# wykonawczy.net
KiCad netlist of a schematic drawn in EAGLE
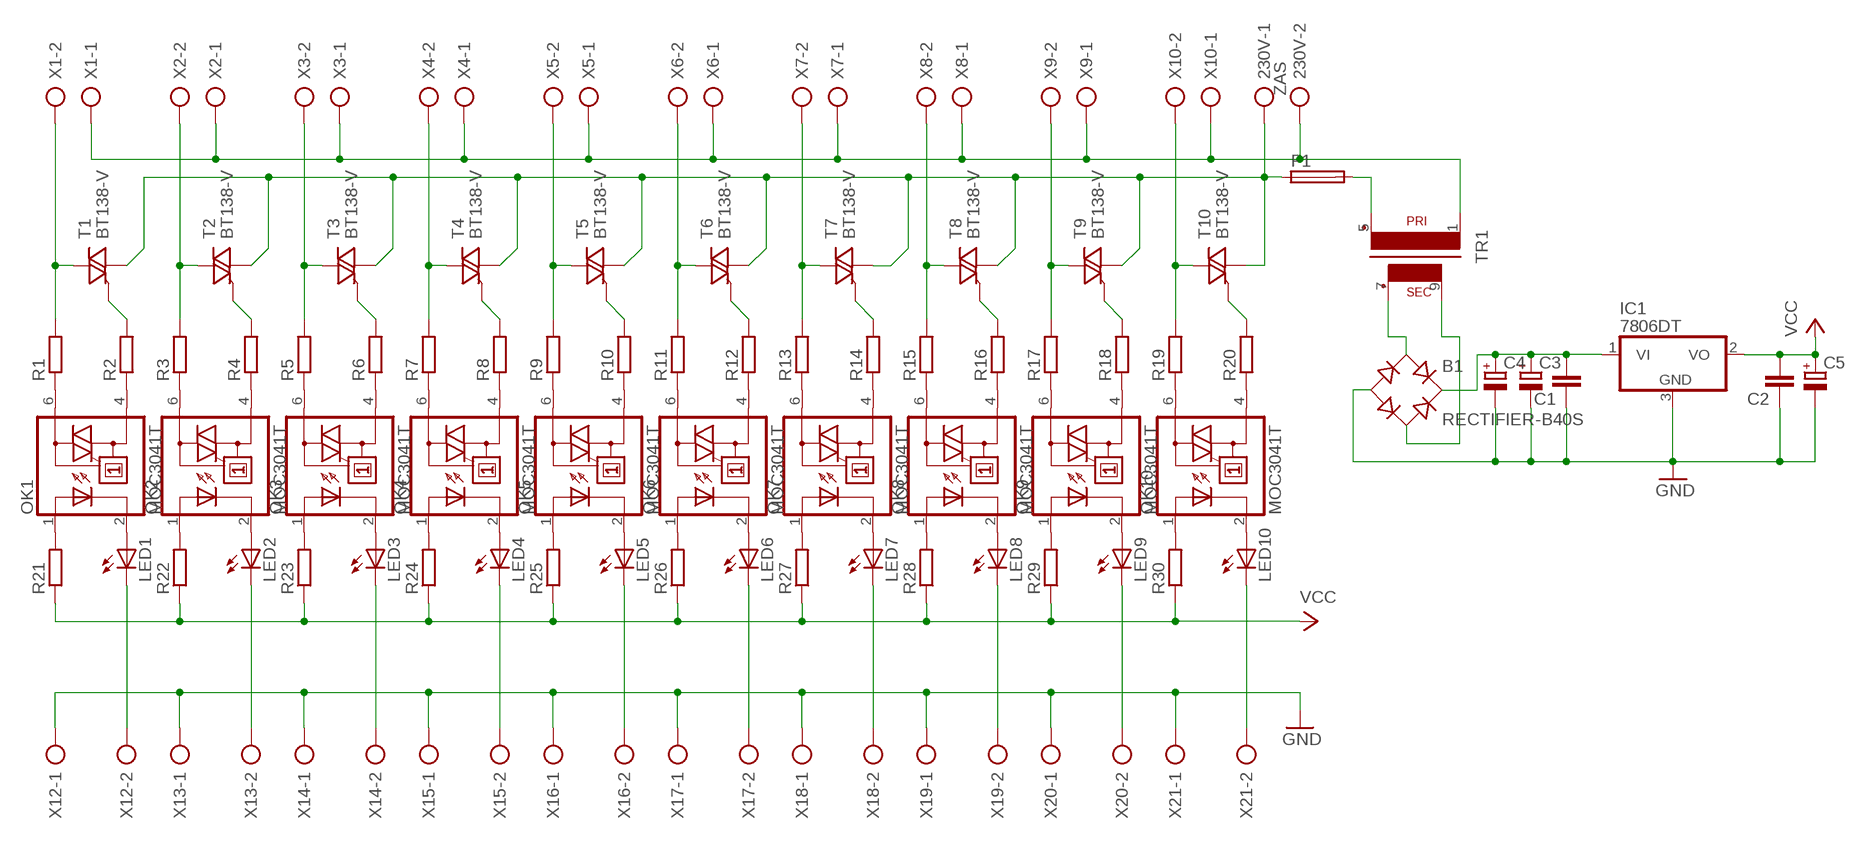
[diagram p0: schematic, sheet 1]

(export (version "E")
  (design (tool "Eeschema 10.0.6"))
  (components
    (comp (ref "230V")
      (value "ZAS")
      (footprint "eagle-import:AK500_2")
      (libsource (lib "eagle-import") (part "AK500/2"))
    )
    (comp (ref "B1")
      (value "RECTIFIER-B40S")
      (footprint "eagle-import:B40S")
      (libsource (lib "eagle-import") (part "RECTIFIER-B40S"))
    )
    (comp (ref "C1")
      (value "C-EU025-025X050")
      (footprint "eagle-import:C025-025X050")
      (libsource (lib "eagle-import") (part "C-EU025-025X050"))
    )
    (comp (ref "C2")
      (value "C-EU025-025X050")
      (footprint "eagle-import:C025-025X050")
      (libsource (lib "eagle-import") (part "C-EU025-025X050"))
    )
    (comp (ref "C3")
      (value "CPOL-EUE2.5-6")
      (footprint "eagle-import:E2,5-6")
      (libsource (lib "eagle-import") (part "CPOL-EUE2.5-6"))
    )
    (comp (ref "C4")
      (value "CPOL-EUE2.5-6")
      (footprint "eagle-import:E2,5-6")
      (libsource (lib "eagle-import") (part "CPOL-EUE2.5-6"))
    )
    (comp (ref "C5")
      (value "CPOL-EUE2.5-6")
      (footprint "eagle-import:E2,5-6")
      (libsource (lib "eagle-import") (part "CPOL-EUE2.5-6"))
    )
    (comp (ref "F1")
      (value "19560")
      (footprint "eagle-import:19560")
      (fields (field (name "MPN") "56000001009"))
      (libsource (lib "eagle-import") (part "19560"))
    )
    (comp (ref "IC1")
      (value "7806DT")
      (footprint "eagle-import:TO252")
      (libsource (lib "eagle-import") (part "78DT06"))
    )
    (comp (ref "LED1")
      (value "LED5MM")
      (footprint "eagle-import:LED5MM")
      (libsource (lib "eagle-import") (part "LED5MM"))
    )
    (comp (ref "LED2")
      (value "LED5MM")
      (footprint "eagle-import:LED5MM")
      (libsource (lib "eagle-import") (part "LED5MM"))
    )
    (comp (ref "LED3")
      (value "LED5MM")
      (footprint "eagle-import:LED5MM")
      (libsource (lib "eagle-import") (part "LED5MM"))
    )
    (comp (ref "LED4")
      (value "LED5MM")
      (footprint "eagle-import:LED5MM")
      (libsource (lib "eagle-import") (part "LED5MM"))
    )
    (comp (ref "LED5")
      (value "LED5MM")
      (footprint "eagle-import:LED5MM")
      (libsource (lib "eagle-import") (part "LED5MM"))
    )
    (comp (ref "LED6")
      (value "LED5MM")
      (footprint "eagle-import:LED5MM")
      (libsource (lib "eagle-import") (part "LED5MM"))
    )
    (comp (ref "LED7")
      (value "LED5MM")
      (footprint "eagle-import:LED5MM")
      (libsource (lib "eagle-import") (part "LED5MM"))
    )
    (comp (ref "LED8")
      (value "LED5MM")
      (footprint "eagle-import:LED5MM")
      (libsource (lib "eagle-import") (part "LED5MM"))
    )
    (comp (ref "LED9")
      (value "LED5MM")
      (footprint "eagle-import:LED5MM")
      (libsource (lib "eagle-import") (part "LED5MM"))
    )
    (comp (ref "LED10")
      (value "LED5MM")
      (footprint "eagle-import:LED5MM")
      (libsource (lib "eagle-import") (part "LED5MM"))
    )
    (comp (ref "OK1")
      (value "MOC3041T")
      (footprint "eagle-import:DIL06B")
      (libsource (lib "eagle-import") (part "MOC30T41"))
    )
    (comp (ref "OK2")
      (value "MOC3041T")
      (footprint "eagle-import:DIL06B")
      (libsource (lib "eagle-import") (part "MOC30T41"))
    )
    (comp (ref "OK3")
      (value "MOC3041T")
      (footprint "eagle-import:DIL06B")
      (libsource (lib "eagle-import") (part "MOC30T41"))
    )
    (comp (ref "OK4")
      (value "MOC3041T")
      (footprint "eagle-import:DIL06B")
      (libsource (lib "eagle-import") (part "MOC30T41"))
    )
    (comp (ref "OK5")
      (value "MOC3041T")
      (footprint "eagle-import:DIL06B")
      (libsource (lib "eagle-import") (part "MOC30T41"))
    )
    (comp (ref "OK6")
      (value "MOC3041T")
      (footprint "eagle-import:DIL06B")
      (libsource (lib "eagle-import") (part "MOC30T41"))
    )
    (comp (ref "OK7")
      (value "MOC3041T")
      (footprint "eagle-import:DIL06B")
      (libsource (lib "eagle-import") (part "MOC30T41"))
    )
    (comp (ref "OK8")
      (value "MOC3041T")
      (footprint "eagle-import:DIL06B")
      (libsource (lib "eagle-import") (part "MOC30T41"))
    )
    (comp (ref "OK9")
      (value "MOC3041T")
      (footprint "eagle-import:DIL06B")
      (libsource (lib "eagle-import") (part "MOC30T41"))
    )
    (comp (ref "OK10")
      (value "MOC3041T")
      (footprint "eagle-import:DIL06B")
      (libsource (lib "eagle-import") (part "MOC30T41"))
    )
    (comp (ref "R1")
      (value "R-EU_0204/7")
      (footprint "eagle-import:0204_7")
      (libsource (lib "eagle-import") (part "R-EU_0204/7"))
    )
    (comp (ref "R2")
      (value "R-EU_0204/7")
      (footprint "eagle-import:0204_7")
      (libsource (lib "eagle-import") (part "R-EU_0204/7"))
    )
    (comp (ref "R3")
      (value "R-EU_0204/7")
      (footprint "eagle-import:0204_7")
      (libsource (lib "eagle-import") (part "R-EU_0204/7"))
    )
    (comp (ref "R4")
      (value "R-EU_0204/7")
      (footprint "eagle-import:0204_7")
      (libsource (lib "eagle-import") (part "R-EU_0204/7"))
    )
    (comp (ref "R5")
      (value "R-EU_0204/7")
      (footprint "eagle-import:0204_7")
      (libsource (lib "eagle-import") (part "R-EU_0204/7"))
    )
    (comp (ref "R6")
      (value "R-EU_0204/7")
      (footprint "eagle-import:0204_7")
      (libsource (lib "eagle-import") (part "R-EU_0204/7"))
    )
    (comp (ref "R7")
      (value "R-EU_0204/7")
      (footprint "eagle-import:0204_7")
      (libsource (lib "eagle-import") (part "R-EU_0204/7"))
    )
    (comp (ref "R8")
      (value "R-EU_0204/7")
      (footprint "eagle-import:0204_7")
      (libsource (lib "eagle-import") (part "R-EU_0204/7"))
    )
    (comp (ref "R9")
      (value "R-EU_0204/7")
      (footprint "eagle-import:0204_7")
      (libsource (lib "eagle-import") (part "R-EU_0204/7"))
    )
    (comp (ref "R10")
      (value "R-EU_0204/7")
      (footprint "eagle-import:0204_7")
      (libsource (lib "eagle-import") (part "R-EU_0204/7"))
    )
    (comp (ref "R11")
      (value "R-EU_0204/7")
      (footprint "eagle-import:0204_7")
      (libsource (lib "eagle-import") (part "R-EU_0204/7"))
    )
    (comp (ref "R12")
      (value "R-EU_0204/7")
      (footprint "eagle-import:0204_7")
      (libsource (lib "eagle-import") (part "R-EU_0204/7"))
    )
    (comp (ref "R13")
      (value "R-EU_0204/7")
      (footprint "eagle-import:0204_7")
      (libsource (lib "eagle-import") (part "R-EU_0204/7"))
    )
    (comp (ref "R14")
      (value "R-EU_0204/7")
      (footprint "eagle-import:0204_7")
      (libsource (lib "eagle-import") (part "R-EU_0204/7"))
    )
    (comp (ref "R15")
      (value "R-EU_0204/7")
      (footprint "eagle-import:0204_7")
      (libsource (lib "eagle-import") (part "R-EU_0204/7"))
    )
    (comp (ref "R16")
      (value "R-EU_0204/7")
      (footprint "eagle-import:0204_7")
      (libsource (lib "eagle-import") (part "R-EU_0204/7"))
    )
    (comp (ref "R17")
      (value "R-EU_0204/7")
      (footprint "eagle-import:0204_7")
      (libsource (lib "eagle-import") (part "R-EU_0204/7"))
    )
    (comp (ref "R18")
      (value "R-EU_0204/7")
      (footprint "eagle-import:0204_7")
      (libsource (lib "eagle-import") (part "R-EU_0204/7"))
    )
    (comp (ref "R19")
      (value "R-EU_0204/7")
      (footprint "eagle-import:0204_7")
      (libsource (lib "eagle-import") (part "R-EU_0204/7"))
    )
    (comp (ref "R20")
      (value "R-EU_0204/7")
      (footprint "eagle-import:0204_7")
      (libsource (lib "eagle-import") (part "R-EU_0204/7"))
    )
    (comp (ref "R21")
      (value "R-EU_0204/7")
      (footprint "eagle-import:0204_7")
      (libsource (lib "eagle-import") (part "R-EU_0204/7"))
    )
    (comp (ref "R22")
      (value "R-EU_0204/7")
      (footprint "eagle-import:0204_7")
      (libsource (lib "eagle-import") (part "R-EU_0204/7"))
    )
    (comp (ref "R23")
      (value "R-EU_0204/7")
      (footprint "eagle-import:0204_7")
      (libsource (lib "eagle-import") (part "R-EU_0204/7"))
    )
    (comp (ref "R24")
      (value "R-EU_0204/7")
      (footprint "eagle-import:0204_7")
      (libsource (lib "eagle-import") (part "R-EU_0204/7"))
    )
    (comp (ref "R25")
      (value "R-EU_0204/7")
      (footprint "eagle-import:0204_7")
      (libsource (lib "eagle-import") (part "R-EU_0204/7"))
    )
    (comp (ref "R26")
      (value "R-EU_0204/7")
      (footprint "eagle-import:0204_7")
      (libsource (lib "eagle-import") (part "R-EU_0204/7"))
    )
    (comp (ref "R27")
      (value "R-EU_0204/7")
      (footprint "eagle-import:0204_7")
      (libsource (lib "eagle-import") (part "R-EU_0204/7"))
    )
    (comp (ref "R28")
      (value "R-EU_0204/7")
      (footprint "eagle-import:0204_7")
      (libsource (lib "eagle-import") (part "R-EU_0204/7"))
    )
    (comp (ref "R29")
      (value "R-EU_0204/7")
      (footprint "eagle-import:0204_7")
      (libsource (lib "eagle-import") (part "R-EU_0204/7"))
    )
    (comp (ref "R30")
      (value "R-EU_0204/7")
      (footprint "eagle-import:0204_7")
      (libsource (lib "eagle-import") (part "R-EU_0204/7"))
    )
    (comp (ref "T1")
      (value "BT138-V")
      (footprint "eagle-import:TO220BV")
      (libsource (lib "eagle-import") (part "BT138-V"))
    )
    (comp (ref "T2")
      (value "BT138-V")
      (footprint "eagle-import:TO220BV")
      (libsource (lib "eagle-import") (part "BT138-V"))
    )
    (comp (ref "T3")
      (value "BT138-V")
      (footprint "eagle-import:TO220BV")
      (libsource (lib "eagle-import") (part "BT138-V"))
    )
    (comp (ref "T4")
      (value "BT138-V")
      (footprint "eagle-import:TO220BV")
      (libsource (lib "eagle-import") (part "BT138-V"))
    )
    (comp (ref "T5")
      (value "BT138-V")
      (footprint "eagle-import:TO220BV")
      (libsource (lib "eagle-import") (part "BT138-V"))
    )
    (comp (ref "T6")
      (value "BT138-V")
      (footprint "eagle-import:TO220BV")
      (libsource (lib "eagle-import") (part "BT138-V"))
    )
    (comp (ref "T7")
      (value "BT138-V")
      (footprint "eagle-import:TO220BV")
      (libsource (lib "eagle-import") (part "BT138-V"))
    )
    (comp (ref "T8")
      (value "BT138-V")
      (footprint "eagle-import:TO220BV")
      (libsource (lib "eagle-import") (part "BT138-V"))
    )
    (comp (ref "T9")
      (value "BT138-V")
      (footprint "eagle-import:TO220BV")
      (libsource (lib "eagle-import") (part "BT138-V"))
    )
    (comp (ref "T10")
      (value "BT138-V")
      (footprint "eagle-import:TO220BV")
      (libsource (lib "eagle-import") (part "BT138-V"))
    )
    (comp (ref "TR1")
      (value "EI30-1")
      (footprint "eagle-import:EI30-1")
      (libsource (lib "eagle-import") (part "EI30-1"))
    )
    (comp (ref "X1")
      (value "AK500/2")
      (footprint "eagle-import:AK500_2")
      (libsource (lib "eagle-import") (part "AK500/2"))
    )
    (comp (ref "X2")
      (value "AK500/2")
      (footprint "eagle-import:AK500_2")
      (libsource (lib "eagle-import") (part "AK500/2"))
    )
    (comp (ref "X3")
      (value "AK500/2")
      (footprint "eagle-import:AK500_2")
      (libsource (lib "eagle-import") (part "AK500/2"))
    )
    (comp (ref "X4")
      (value "AK500/2")
      (footprint "eagle-import:AK500_2")
      (libsource (lib "eagle-import") (part "AK500/2"))
    )
    (comp (ref "X5")
      (value "AK500/2")
      (footprint "eagle-import:AK500_2")
      (libsource (lib "eagle-import") (part "AK500/2"))
    )
    (comp (ref "X6")
      (value "AK500/2")
      (footprint "eagle-import:AK500_2")
      (libsource (lib "eagle-import") (part "AK500/2"))
    )
    (comp (ref "X7")
      (value "AK500/2")
      (footprint "eagle-import:AK500_2")
      (libsource (lib "eagle-import") (part "AK500/2"))
    )
    (comp (ref "X8")
      (value "AK500/2")
      (footprint "eagle-import:AK500_2")
      (libsource (lib "eagle-import") (part "AK500/2"))
    )
    (comp (ref "X9")
      (value "AK500/2")
      (footprint "eagle-import:AK500_2")
      (libsource (lib "eagle-import") (part "AK500/2"))
    )
    (comp (ref "X10")
      (value "AK500/2")
      (footprint "eagle-import:AK500_2")
      (libsource (lib "eagle-import") (part "AK500/2"))
    )
    (comp (ref "X12")
      (value "AK500/2")
      (footprint "eagle-import:AK500_2")
      (libsource (lib "eagle-import") (part "AK500/2"))
    )
    (comp (ref "X13")
      (value "AK500/2")
      (footprint "eagle-import:AK500_2")
      (libsource (lib "eagle-import") (part "AK500/2"))
    )
    (comp (ref "X14")
      (value "AK500/2")
      (footprint "eagle-import:AK500_2")
      (libsource (lib "eagle-import") (part "AK500/2"))
    )
    (comp (ref "X15")
      (value "AK500/2")
      (footprint "eagle-import:AK500_2")
      (libsource (lib "eagle-import") (part "AK500/2"))
    )
    (comp (ref "X16")
      (value "AK500/2")
      (footprint "eagle-import:AK500_2")
      (libsource (lib "eagle-import") (part "AK500/2"))
    )
    (comp (ref "X17")
      (value "AK500/2")
      (footprint "eagle-import:AK500_2")
      (libsource (lib "eagle-import") (part "AK500/2"))
    )
    (comp (ref "X18")
      (value "AK500/2")
      (footprint "eagle-import:AK500_2")
      (libsource (lib "eagle-import") (part "AK500/2"))
    )
    (comp (ref "X19")
      (value "AK500/2")
      (footprint "eagle-import:AK500_2")
      (libsource (lib "eagle-import") (part "AK500/2"))
    )
    (comp (ref "X20")
      (value "AK500/2")
      (footprint "eagle-import:AK500_2")
      (libsource (lib "eagle-import") (part "AK500/2"))
    )
    (comp (ref "X21")
      (value "AK500/2")
      (footprint "eagle-import:AK500_2")
      (libsource (lib "eagle-import") (part "AK500/2"))
    )
  )
  (nets
    (net (code "1") (name "GND") (class "Default")
      (node (ref "B1") (pin "-") (pinfunction "-_-") (pintype "passive"))
      (node (ref "C1") (pin "1") (pinfunction "1_1") (pintype "passive"))
      (node (ref "C2") (pin "1") (pinfunction "1_1") (pintype "passive"))
      (node (ref "C3") (pin "-") (pinfunction "-_-") (pintype "passive"))
      (node (ref "C4") (pin "-") (pinfunction "-_-") (pintype "passive"))
      (node (ref "C5") (pin "-") (pinfunction "-_-") (pintype "passive"))
      (node (ref "IC1") (pin "3") (pinfunction "GND_3") (pintype "passive"))
      (node (ref "X12") (pin "1") (pinfunction "KL_1") (pintype "passive"))
      (node (ref "X13") (pin "1") (pinfunction "KL_1") (pintype "passive"))
      (node (ref "X14") (pin "1") (pinfunction "KL_1") (pintype "passive"))
      (node (ref "X15") (pin "1") (pinfunction "KL_1") (pintype "passive"))
      (node (ref "X16") (pin "1") (pinfunction "KL_1") (pintype "passive"))
      (node (ref "X17") (pin "1") (pinfunction "KL_1") (pintype "passive"))
      (node (ref "X18") (pin "1") (pinfunction "KL_1") (pintype "passive"))
      (node (ref "X19") (pin "1") (pinfunction "KL_1") (pintype "passive"))
      (node (ref "X20") (pin "1") (pinfunction "KL_1") (pintype "passive"))
      (node (ref "X21") (pin "1") (pinfunction "KL_1") (pintype "passive"))
    )
    (net (code "2") (name "Net-(230VA-KL)") (class "Default")
      (node (ref "230V") (pin "1") (pinfunction "KL_1") (pintype "passive"))
      (node (ref "F1") (pin "1") (pinfunction "1_1") (pintype "passive"))
      (node (ref "T1") (pin "T1") (pinfunction "A1_T1") (pintype "passive"))
      (node (ref "T10") (pin "T1") (pinfunction "A1_T1") (pintype "passive"))
      (node (ref "T2") (pin "T1") (pinfunction "A1_T1") (pintype "passive"))
      (node (ref "T3") (pin "T1") (pinfunction "A1_T1") (pintype "passive"))
      (node (ref "T4") (pin "T1") (pinfunction "A1_T1") (pintype "passive"))
      (node (ref "T5") (pin "T1") (pinfunction "A1_T1") (pintype "passive"))
      (node (ref "T6") (pin "T1") (pinfunction "A1_T1") (pintype "passive"))
      (node (ref "T7") (pin "T1") (pinfunction "A1_T1") (pintype "passive"))
      (node (ref "T8") (pin "T1") (pinfunction "A1_T1") (pintype "passive"))
      (node (ref "T9") (pin "T1") (pinfunction "A1_T1") (pintype "passive"))
    )
    (net (code "3") (name "Net-(230VB-KL)") (class "Default")
      (node (ref "230V") (pin "2") (pinfunction "KL_2") (pintype "passive"))
      (node (ref "TR1") (pin "1") (pinfunction "P1_1") (pintype "passive"))
      (node (ref "X1") (pin "1") (pinfunction "KL_1") (pintype "passive"))
      (node (ref "X10") (pin "1") (pinfunction "KL_1") (pintype "passive"))
      (node (ref "X2") (pin "1") (pinfunction "KL_1") (pintype "passive"))
      (node (ref "X3") (pin "1") (pinfunction "KL_1") (pintype "passive"))
      (node (ref "X4") (pin "1") (pinfunction "KL_1") (pintype "passive"))
      (node (ref "X5") (pin "1") (pinfunction "KL_1") (pintype "passive"))
      (node (ref "X6") (pin "1") (pinfunction "KL_1") (pintype "passive"))
      (node (ref "X7") (pin "1") (pinfunction "KL_1") (pintype "passive"))
      (node (ref "X8") (pin "1") (pinfunction "KL_1") (pintype "passive"))
      (node (ref "X9") (pin "1") (pinfunction "KL_1") (pintype "passive"))
    )
    (net (code "4") (name "Net-(IC1-VI)") (class "Default")
      (node (ref "B1") (pin "+") (pinfunction "+_+") (pintype "passive"))
      (node (ref "C1") (pin "2") (pinfunction "2_2") (pintype "passive"))
      (node (ref "C3") (pin "+") (pinfunction "+_+") (pintype "passive"))
      (node (ref "C4") (pin "+") (pinfunction "+_+") (pintype "passive"))
      (node (ref "IC1") (pin "1") (pinfunction "VI_1") (pintype "input"))
    )
    (net (code "5") (name "Net-(LED1-C)") (class "Default")
      (node (ref "LED1") (pin "K") (pinfunction "C_K") (pintype "passive"))
      (node (ref "X12") (pin "2") (pinfunction "KL_2") (pintype "passive"))
    )
    (net (code "6") (name "Net-(LED2-C)") (class "Default")
      (node (ref "LED2") (pin "K") (pinfunction "C_K") (pintype "passive"))
      (node (ref "X13") (pin "2") (pinfunction "KL_2") (pintype "passive"))
    )
    (net (code "7") (name "Net-(LED3-C)") (class "Default")
      (node (ref "LED3") (pin "K") (pinfunction "C_K") (pintype "passive"))
      (node (ref "X14") (pin "2") (pinfunction "KL_2") (pintype "passive"))
    )
    (net (code "8") (name "Net-(LED4-C)") (class "Default")
      (node (ref "LED4") (pin "K") (pinfunction "C_K") (pintype "passive"))
      (node (ref "X15") (pin "2") (pinfunction "KL_2") (pintype "passive"))
    )
    (net (code "9") (name "Net-(LED5-C)") (class "Default")
      (node (ref "LED5") (pin "K") (pinfunction "C_K") (pintype "passive"))
      (node (ref "X16") (pin "2") (pinfunction "KL_2") (pintype "passive"))
    )
    (net (code "10") (name "Net-(LED6-C)") (class "Default")
      (node (ref "LED6") (pin "K") (pinfunction "C_K") (pintype "passive"))
      (node (ref "X17") (pin "2") (pinfunction "KL_2") (pintype "passive"))
    )
    (net (code "11") (name "Net-(LED7-C)") (class "Default")
      (node (ref "LED7") (pin "K") (pinfunction "C_K") (pintype "passive"))
      (node (ref "X18") (pin "2") (pinfunction "KL_2") (pintype "passive"))
    )
    (net (code "12") (name "Net-(LED8-C)") (class "Default")
      (node (ref "LED8") (pin "K") (pinfunction "C_K") (pintype "passive"))
      (node (ref "X19") (pin "2") (pinfunction "KL_2") (pintype "passive"))
    )
    (net (code "13") (name "Net-(LED9-C)") (class "Default")
      (node (ref "LED9") (pin "K") (pinfunction "C_K") (pintype "passive"))
      (node (ref "X20") (pin "2") (pinfunction "KL_2") (pintype "passive"))
    )
    (net (code "14") (name "Net-(LED10-C)") (class "Default")
      (node (ref "LED10") (pin "K") (pinfunction "C_K") (pintype "passive"))
      (node (ref "X21") (pin "2") (pinfunction "KL_2") (pintype "passive"))
    )
    (net (code "15") (name "Net-(OK1-A)") (class "Default")
      (node (ref "OK1") (pin "1") (pinfunction "A_1") (pintype "passive"))
      (node (ref "R21") (pin "2") (pinfunction "2_2") (pintype "passive"))
    )
    (net (code "16") (name "Net-(OK1-A1)") (class "Default")
      (node (ref "OK1") (pin "4") (pinfunction "A1_4") (pintype "passive"))
      (node (ref "R2") (pin "1") (pinfunction "1_1") (pintype "passive"))
    )
    (net (code "17") (name "Net-(OK1-A2)") (class "Default")
      (node (ref "OK1") (pin "6") (pinfunction "A2_6") (pintype "passive"))
      (node (ref "R1") (pin "1") (pinfunction "1_1") (pintype "passive"))
    )
    (net (code "18") (name "Net-(OK1-C)") (class "Default")
      (node (ref "LED1") (pin "A") (pinfunction "A_A") (pintype "passive"))
      (node (ref "OK1") (pin "2") (pinfunction "C_2") (pintype "passive"))
    )
    (net (code "19") (name "Net-(OK2-A)") (class "Default")
      (node (ref "OK2") (pin "1") (pinfunction "A_1") (pintype "passive"))
      (node (ref "R22") (pin "2") (pinfunction "2_2") (pintype "passive"))
    )
    (net (code "20") (name "Net-(OK2-A1)") (class "Default")
      (node (ref "OK2") (pin "4") (pinfunction "A1_4") (pintype "passive"))
      (node (ref "R4") (pin "1") (pinfunction "1_1") (pintype "passive"))
    )
    (net (code "21") (name "Net-(OK2-A2)") (class "Default")
      (node (ref "OK2") (pin "6") (pinfunction "A2_6") (pintype "passive"))
      (node (ref "R3") (pin "1") (pinfunction "1_1") (pintype "passive"))
    )
    (net (code "22") (name "Net-(OK2-C)") (class "Default")
      (node (ref "LED2") (pin "A") (pinfunction "A_A") (pintype "passive"))
      (node (ref "OK2") (pin "2") (pinfunction "C_2") (pintype "passive"))
    )
    (net (code "23") (name "Net-(OK3-A)") (class "Default")
      (node (ref "OK3") (pin "1") (pinfunction "A_1") (pintype "passive"))
      (node (ref "R23") (pin "2") (pinfunction "2_2") (pintype "passive"))
    )
    (net (code "24") (name "Net-(OK3-A1)") (class "Default")
      (node (ref "OK3") (pin "4") (pinfunction "A1_4") (pintype "passive"))
      (node (ref "R6") (pin "1") (pinfunction "1_1") (pintype "passive"))
    )
    (net (code "25") (name "Net-(OK3-A2)") (class "Default")
      (node (ref "OK3") (pin "6") (pinfunction "A2_6") (pintype "passive"))
      (node (ref "R5") (pin "1") (pinfunction "1_1") (pintype "passive"))
    )
    (net (code "26") (name "Net-(OK3-C)") (class "Default")
      (node (ref "LED3") (pin "A") (pinfunction "A_A") (pintype "passive"))
      (node (ref "OK3") (pin "2") (pinfunction "C_2") (pintype "passive"))
    )
    (net (code "27") (name "Net-(OK4-A)") (class "Default")
      (node (ref "OK4") (pin "1") (pinfunction "A_1") (pintype "passive"))
      (node (ref "R24") (pin "2") (pinfunction "2_2") (pintype "passive"))
    )
    (net (code "28") (name "Net-(OK4-A1)") (class "Default")
      (node (ref "OK4") (pin "4") (pinfunction "A1_4") (pintype "passive"))
      (node (ref "R8") (pin "1") (pinfunction "1_1") (pintype "passive"))
    )
    (net (code "29") (name "Net-(OK4-A2)") (class "Default")
      (node (ref "OK4") (pin "6") (pinfunction "A2_6") (pintype "passive"))
      (node (ref "R7") (pin "1") (pinfunction "1_1") (pintype "passive"))
    )
    (net (code "30") (name "Net-(OK4-C)") (class "Default")
      (node (ref "LED4") (pin "A") (pinfunction "A_A") (pintype "passive"))
      (node (ref "OK4") (pin "2") (pinfunction "C_2") (pintype "passive"))
    )
    (net (code "31") (name "Net-(OK5-A)") (class "Default")
      (node (ref "OK5") (pin "1") (pinfunction "A_1") (pintype "passive"))
      (node (ref "R25") (pin "2") (pinfunction "2_2") (pintype "passive"))
    )
    (net (code "32") (name "Net-(OK5-A1)") (class "Default")
      (node (ref "OK5") (pin "4") (pinfunction "A1_4") (pintype "passive"))
      (node (ref "R10") (pin "1") (pinfunction "1_1") (pintype "passive"))
    )
    (net (code "33") (name "Net-(OK5-A2)") (class "Default")
      (node (ref "OK5") (pin "6") (pinfunction "A2_6") (pintype "passive"))
      (node (ref "R9") (pin "1") (pinfunction "1_1") (pintype "passive"))
    )
    (net (code "34") (name "Net-(OK5-C)") (class "Default")
      (node (ref "LED5") (pin "A") (pinfunction "A_A") (pintype "passive"))
      (node (ref "OK5") (pin "2") (pinfunction "C_2") (pintype "passive"))
    )
    (net (code "35") (name "Net-(OK6-A)") (class "Default")
      (node (ref "OK6") (pin "1") (pinfunction "A_1") (pintype "passive"))
      (node (ref "R26") (pin "2") (pinfunction "2_2") (pintype "passive"))
    )
    (net (code "36") (name "Net-(OK6-A1)") (class "Default")
      (node (ref "OK6") (pin "4") (pinfunction "A1_4") (pintype "passive"))
      (node (ref "R12") (pin "1") (pinfunction "1_1") (pintype "passive"))
    )
    (net (code "37") (name "Net-(OK6-A2)") (class "Default")
      (node (ref "OK6") (pin "6") (pinfunction "A2_6") (pintype "passive"))
      (node (ref "R11") (pin "1") (pinfunction "1_1") (pintype "passive"))
    )
    (net (code "38") (name "Net-(OK6-C)") (class "Default")
      (node (ref "LED6") (pin "A") (pinfunction "A_A") (pintype "passive"))
      (node (ref "OK6") (pin "2") (pinfunction "C_2") (pintype "passive"))
    )
    (net (code "39") (name "Net-(OK7-A)") (class "Default")
      (node (ref "OK7") (pin "1") (pinfunction "A_1") (pintype "passive"))
      (node (ref "R27") (pin "2") (pinfunction "2_2") (pintype "passive"))
    )
    (net (code "40") (name "Net-(OK7-A1)") (class "Default")
      (node (ref "OK7") (pin "4") (pinfunction "A1_4") (pintype "passive"))
      (node (ref "R14") (pin "1") (pinfunction "1_1") (pintype "passive"))
    )
    (net (code "41") (name "Net-(OK7-A2)") (class "Default")
      (node (ref "OK7") (pin "6") (pinfunction "A2_6") (pintype "passive"))
      (node (ref "R13") (pin "1") (pinfunction "1_1") (pintype "passive"))
    )
    (net (code "42") (name "Net-(OK7-C)") (class "Default")
      (node (ref "LED7") (pin "A") (pinfunction "A_A") (pintype "passive"))
      (node (ref "OK7") (pin "2") (pinfunction "C_2") (pintype "passive"))
    )
    (net (code "43") (name "Net-(OK8-A)") (class "Default")
      (node (ref "OK8") (pin "1") (pinfunction "A_1") (pintype "passive"))
      (node (ref "R28") (pin "2") (pinfunction "2_2") (pintype "passive"))
    )
    (net (code "44") (name "Net-(OK8-A1)") (class "Default")
      (node (ref "OK8") (pin "4") (pinfunction "A1_4") (pintype "passive"))
      (node (ref "R16") (pin "1") (pinfunction "1_1") (pintype "passive"))
    )
    (net (code "45") (name "Net-(OK8-A2)") (class "Default")
      (node (ref "OK8") (pin "6") (pinfunction "A2_6") (pintype "passive"))
      (node (ref "R15") (pin "1") (pinfunction "1_1") (pintype "passive"))
    )
    (net (code "46") (name "Net-(OK8-C)") (class "Default")
      (node (ref "LED8") (pin "A") (pinfunction "A_A") (pintype "passive"))
      (node (ref "OK8") (pin "2") (pinfunction "C_2") (pintype "passive"))
    )
    (net (code "47") (name "Net-(OK9-A)") (class "Default")
      (node (ref "OK9") (pin "1") (pinfunction "A_1") (pintype "passive"))
      (node (ref "R29") (pin "2") (pinfunction "2_2") (pintype "passive"))
    )
    (net (code "48") (name "Net-(OK9-A1)") (class "Default")
      (node (ref "OK9") (pin "4") (pinfunction "A1_4") (pintype "passive"))
      (node (ref "R18") (pin "1") (pinfunction "1_1") (pintype "passive"))
    )
    (net (code "49") (name "Net-(OK9-A2)") (class "Default")
      (node (ref "OK9") (pin "6") (pinfunction "A2_6") (pintype "passive"))
      (node (ref "R17") (pin "1") (pinfunction "1_1") (pintype "passive"))
    )
    (net (code "50") (name "Net-(OK9-C)") (class "Default")
      (node (ref "LED9") (pin "A") (pinfunction "A_A") (pintype "passive"))
      (node (ref "OK9") (pin "2") (pinfunction "C_2") (pintype "passive"))
    )
    (net (code "51") (name "Net-(OK10-A)") (class "Default")
      (node (ref "OK10") (pin "1") (pinfunction "A_1") (pintype "passive"))
      (node (ref "R30") (pin "2") (pinfunction "2_2") (pintype "passive"))
    )
    (net (code "52") (name "Net-(OK10-A1)") (class "Default")
      (node (ref "OK10") (pin "4") (pinfunction "A1_4") (pintype "passive"))
      (node (ref "R20") (pin "1") (pinfunction "1_1") (pintype "passive"))
    )
    (net (code "53") (name "Net-(OK10-A2)") (class "Default")
      (node (ref "OK10") (pin "6") (pinfunction "A2_6") (pintype "passive"))
      (node (ref "R19") (pin "1") (pinfunction "1_1") (pintype "passive"))
    )
    (net (code "54") (name "Net-(OK10-C)") (class "Default")
      (node (ref "LED10") (pin "A") (pinfunction "A_A") (pintype "passive"))
      (node (ref "OK10") (pin "2") (pinfunction "C_2") (pintype "passive"))
    )
    (net (code "55") (name "Net-(R2-Pad2)") (class "Default")
      (node (ref "R2") (pin "2") (pinfunction "2_2") (pintype "passive"))
      (node (ref "T1") (pin "G") (pinfunction "G_G") (pintype "passive"))
    )
    (net (code "56") (name "Net-(R4-Pad2)") (class "Default")
      (node (ref "R4") (pin "2") (pinfunction "2_2") (pintype "passive"))
      (node (ref "T2") (pin "G") (pinfunction "G_G") (pintype "passive"))
    )
    (net (code "57") (name "Net-(R6-Pad2)") (class "Default")
      (node (ref "R6") (pin "2") (pinfunction "2_2") (pintype "passive"))
      (node (ref "T3") (pin "G") (pinfunction "G_G") (pintype "passive"))
    )
    (net (code "58") (name "Net-(R8-Pad2)") (class "Default")
      (node (ref "R8") (pin "2") (pinfunction "2_2") (pintype "passive"))
      (node (ref "T4") (pin "G") (pinfunction "G_G") (pintype "passive"))
    )
    (net (code "59") (name "Net-(R10-Pad2)") (class "Default")
      (node (ref "R10") (pin "2") (pinfunction "2_2") (pintype "passive"))
      (node (ref "T5") (pin "G") (pinfunction "G_G") (pintype "passive"))
    )
    (net (code "60") (name "Net-(R12-Pad2)") (class "Default")
      (node (ref "R12") (pin "2") (pinfunction "2_2") (pintype "passive"))
      (node (ref "T6") (pin "G") (pinfunction "G_G") (pintype "passive"))
    )
    (net (code "61") (name "Net-(R14-Pad2)") (class "Default")
      (node (ref "R14") (pin "2") (pinfunction "2_2") (pintype "passive"))
      (node (ref "T7") (pin "G") (pinfunction "G_G") (pintype "passive"))
    )
    (net (code "62") (name "Net-(R16-Pad2)") (class "Default")
      (node (ref "R16") (pin "2") (pinfunction "2_2") (pintype "passive"))
      (node (ref "T8") (pin "G") (pinfunction "G_G") (pintype "passive"))
    )
    (net (code "63") (name "Net-(R18-Pad2)") (class "Default")
      (node (ref "R18") (pin "2") (pinfunction "2_2") (pintype "passive"))
      (node (ref "T9") (pin "G") (pinfunction "G_G") (pintype "passive"))
    )
    (net (code "64") (name "Net-(R20-Pad2)") (class "Default")
      (node (ref "R20") (pin "2") (pinfunction "2_2") (pintype "passive"))
      (node (ref "T10") (pin "G") (pinfunction "G_G") (pintype "passive"))
    )
    (net (code "65") (name "Net-(T1-A2)") (class "Default")
      (node (ref "R1") (pin "2") (pinfunction "2_2") (pintype "passive"))
      (node (ref "T1") (pin "T2") (pinfunction "A2_T2") (pintype "passive"))
      (node (ref "X1") (pin "2") (pinfunction "KL_2") (pintype "passive"))
    )
    (net (code "66") (name "Net-(T2-A2)") (class "Default")
      (node (ref "R3") (pin "2") (pinfunction "2_2") (pintype "passive"))
      (node (ref "T2") (pin "T2") (pinfunction "A2_T2") (pintype "passive"))
      (node (ref "X2") (pin "2") (pinfunction "KL_2") (pintype "passive"))
    )
    (net (code "67") (name "Net-(T3-A2)") (class "Default")
      (node (ref "R5") (pin "2") (pinfunction "2_2") (pintype "passive"))
      (node (ref "T3") (pin "T2") (pinfunction "A2_T2") (pintype "passive"))
      (node (ref "X3") (pin "2") (pinfunction "KL_2") (pintype "passive"))
    )
    (net (code "68") (name "Net-(T4-A2)") (class "Default")
      (node (ref "R7") (pin "2") (pinfunction "2_2") (pintype "passive"))
      (node (ref "T4") (pin "T2") (pinfunction "A2_T2") (pintype "passive"))
      (node (ref "X4") (pin "2") (pinfunction "KL_2") (pintype "passive"))
    )
    (net (code "69") (name "Net-(T5-A2)") (class "Default")
      (node (ref "R9") (pin "2") (pinfunction "2_2") (pintype "passive"))
      (node (ref "T5") (pin "T2") (pinfunction "A2_T2") (pintype "passive"))
      (node (ref "X5") (pin "2") (pinfunction "KL_2") (pintype "passive"))
    )
    (net (code "70") (name "Net-(T6-A2)") (class "Default")
      (node (ref "R11") (pin "2") (pinfunction "2_2") (pintype "passive"))
      (node (ref "T6") (pin "T2") (pinfunction "A2_T2") (pintype "passive"))
      (node (ref "X6") (pin "2") (pinfunction "KL_2") (pintype "passive"))
    )
    (net (code "71") (name "Net-(T7-A2)") (class "Default")
      (node (ref "R13") (pin "2") (pinfunction "2_2") (pintype "passive"))
      (node (ref "T7") (pin "T2") (pinfunction "A2_T2") (pintype "passive"))
      (node (ref "X7") (pin "2") (pinfunction "KL_2") (pintype "passive"))
    )
    (net (code "72") (name "Net-(T8-A2)") (class "Default")
      (node (ref "R15") (pin "2") (pinfunction "2_2") (pintype "passive"))
      (node (ref "T8") (pin "T2") (pinfunction "A2_T2") (pintype "passive"))
      (node (ref "X8") (pin "2") (pinfunction "KL_2") (pintype "passive"))
    )
    (net (code "73") (name "Net-(T9-A2)") (class "Default")
      (node (ref "R17") (pin "2") (pinfunction "2_2") (pintype "passive"))
      (node (ref "T9") (pin "T2") (pinfunction "A2_T2") (pintype "passive"))
      (node (ref "X9") (pin "2") (pinfunction "KL_2") (pintype "passive"))
    )
    (net (code "74") (name "Net-(T10-A2)") (class "Default")
      (node (ref "R19") (pin "2") (pinfunction "2_2") (pintype "passive"))
      (node (ref "T10") (pin "T2") (pinfunction "A2_T2") (pintype "passive"))
      (node (ref "X10") (pin "2") (pinfunction "KL_2") (pintype "passive"))
    )
    (net (code "75") (name "Net-(TR1-P2)") (class "Default")
      (node (ref "F1") (pin "2") (pinfunction "2_2") (pintype "passive"))
      (node (ref "TR1") (pin "5") (pinfunction "P2_5") (pintype "passive"))
    )
    (net (code "76") (name "Net-(TR1-S3)") (class "Default")
      (node (ref "B1") (pin "AC1") (pinfunction "AC1_AC1") (pintype "passive"))
      (node (ref "TR1") (pin "7") (pinfunction "S3_7") (pintype "passive"))
    )
    (net (code "77") (name "Net-(TR1-S4)") (class "Default")
      (node (ref "B1") (pin "AC2") (pinfunction "AC2_AC2") (pintype "passive"))
      (node (ref "TR1") (pin "9") (pinfunction "S4_9") (pintype "passive"))
    )
    (net (code "78") (name "VCC") (class "Default")
      (node (ref "C2") (pin "2") (pinfunction "2_2") (pintype "passive"))
      (node (ref "C5") (pin "+") (pinfunction "+_+") (pintype "passive"))
      (node (ref "IC1") (pin "2") (pinfunction "VO_2") (pintype "passive"))
      (node (ref "R21") (pin "1") (pinfunction "1_1") (pintype "passive"))
      (node (ref "R22") (pin "1") (pinfunction "1_1") (pintype "passive"))
      (node (ref "R23") (pin "1") (pinfunction "1_1") (pintype "passive"))
      (node (ref "R24") (pin "1") (pinfunction "1_1") (pintype "passive"))
      (node (ref "R25") (pin "1") (pinfunction "1_1") (pintype "passive"))
      (node (ref "R26") (pin "1") (pinfunction "1_1") (pintype "passive"))
      (node (ref "R27") (pin "1") (pinfunction "1_1") (pintype "passive"))
      (node (ref "R28") (pin "1") (pinfunction "1_1") (pintype "passive"))
      (node (ref "R29") (pin "1") (pinfunction "1_1") (pintype "passive"))
      (node (ref "R30") (pin "1") (pinfunction "1_1") (pintype "passive"))
    )
  )
)
